# RiskChemi_Sensors_V2_12.net
KiCad netlist of a schematic drawn in Altium Designer
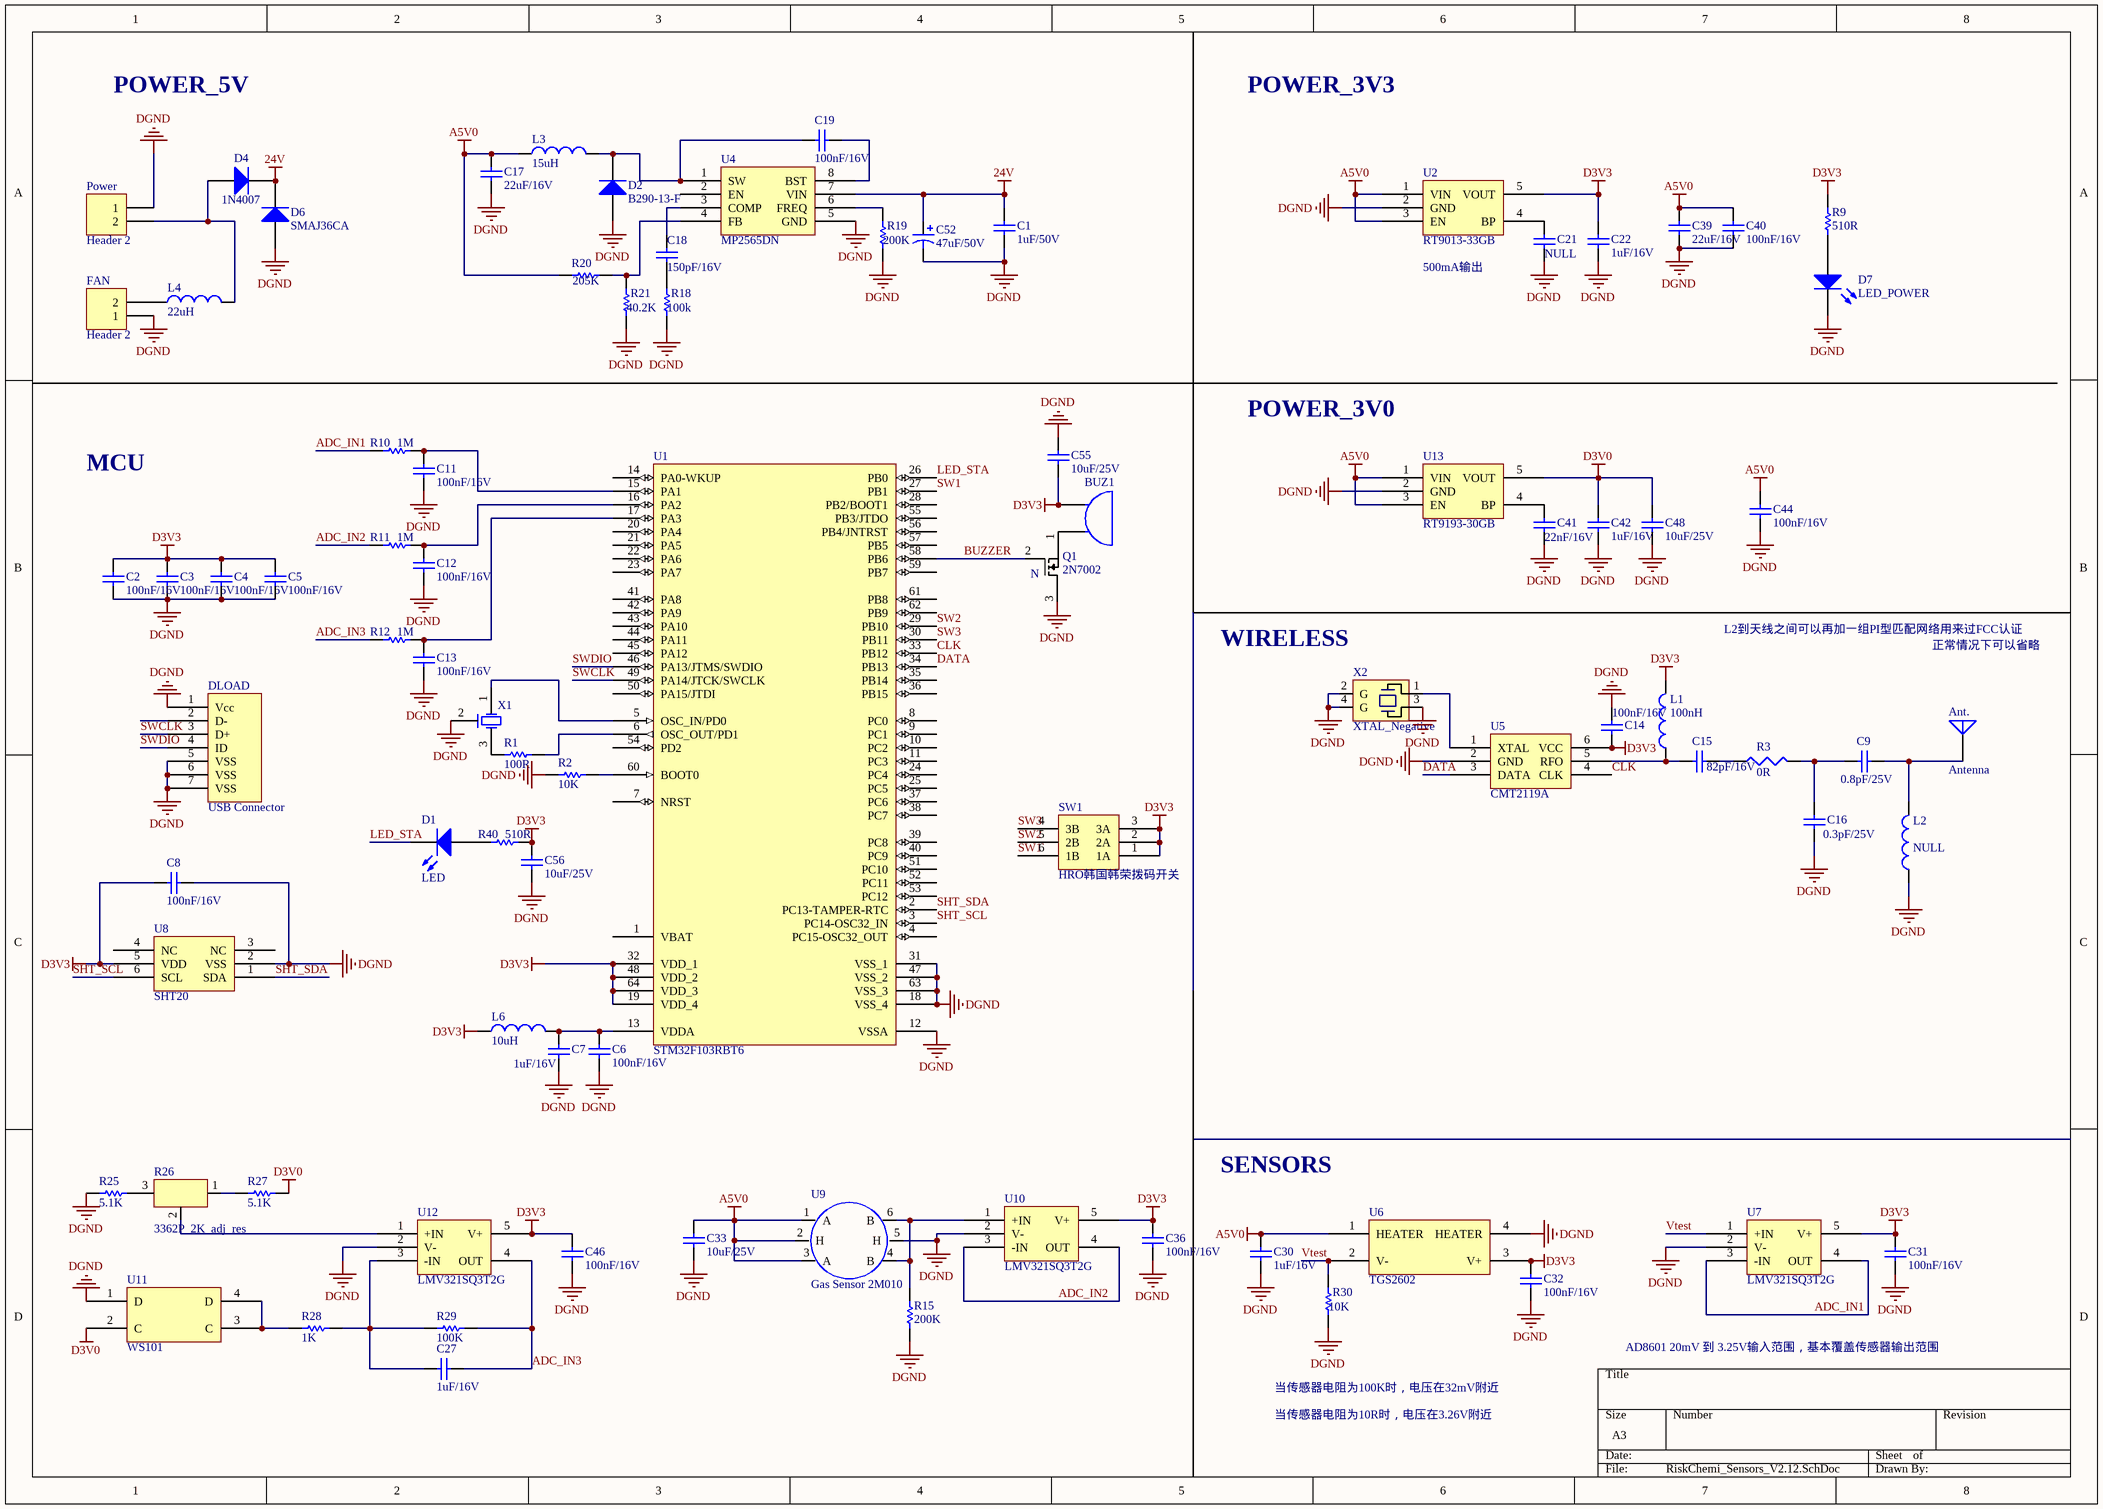
[diagram p0: RiskChemi_Sensors_V2.12.SchDoc]

(export (version "E")
  (design (tool "Eeschema 10.0.6"))
  (components
    (comp (ref "Ant.")
      (value "Antenna")
      (footprint "PIN1")
      (description "Generic Antenna")
      (fields (field (name "PUBLISHER") "Altium Limited"))
      (libsource (lib "Miscellaneous Devices") (part "Antenna"))
    )
    (comp (ref "BUZ1")
      (value "BUZZER 0905 through hole")
      (footprint "BUZ0905")
      (description "Buzzer")
      (libsource (lib "杂元件库") (part "BUZZER"))
    )
    (comp (ref "C1")
      (value "1uF/50V")
      (footprint "0805")
      (description "Capacitor")
      (fields (field (name "PUBLISHER") "Altium Limited"))
      (libsource (lib "Miscellaneous Devices") (part "Cap"))
    )
    (comp (ref "C2")
      (value "100nF/16V")
      (footprint "BinFeng:0603")
      (description "Capacitor")
      (fields (field (name "PUBLISHER") "Altium Limited"))
      (libsource (lib "Miscellaneous Devices") (part "Cap"))
    )
    (comp (ref "C3")
      (value "100nF/16V")
      (footprint "BinFeng:0603")
      (description "Capacitor")
      (fields (field (name "PUBLISHER") "Altium Limited"))
      (libsource (lib "Miscellaneous Devices") (part "Cap"))
    )
    (comp (ref "C4")
      (value "100nF/16V")
      (footprint "BinFeng:0603")
      (description "Capacitor")
      (fields (field (name "PUBLISHER") "Altium Limited"))
      (libsource (lib "Miscellaneous Devices") (part "Cap"))
    )
    (comp (ref "C5")
      (value "100nF/16V")
      (footprint "BinFeng:0603")
      (description "Capacitor")
      (fields (field (name "PUBLISHER") "Altium Limited"))
      (libsource (lib "Miscellaneous Devices") (part "Cap"))
    )
    (comp (ref "C6")
      (value "100nF/16V")
      (footprint "BinFeng:0603")
      (description "Capacitor")
      (fields (field (name "PUBLISHER") "Altium Limited"))
      (libsource (lib "Miscellaneous Devices") (part "Cap"))
    )
    (comp (ref "C7")
      (value "1uF/16V")
      (footprint "BinFeng:0603")
      (description "Capacitor")
      (fields (field (name "PUBLISHER") "Altium Limited"))
      (libsource (lib "Miscellaneous Devices") (part "Cap"))
    )
    (comp (ref "C8")
      (value "100nF/16V")
      (footprint "BinFeng:0603")
      (description "Capacitor")
      (fields (field (name "PUBLISHER") "Altium Limited"))
      (libsource (lib "Miscellaneous Devices") (part "Cap"))
    )
    (comp (ref "C9")
      (value "0.8pF/25V")
      (footprint "1608[0603]")
      (description "Capacitor (Semiconductor SIM Model)")
      (fields (field (name "PUBLISHER") "Altium Limited"))
      (libsource (lib "Miscellaneous Devices") (part "Cap Semi"))
    )
    (comp (ref "C11")
      (value "100nF/16V")
      (footprint "BinFeng:0603")
      (description "Capacitor")
      (fields (field (name "PUBLISHER") "Altium Limited"))
      (libsource (lib "Miscellaneous Devices") (part "Cap"))
    )
    (comp (ref "C12")
      (value "100nF/16V")
      (footprint "BinFeng:0603")
      (description "Capacitor")
      (fields (field (name "PUBLISHER") "Altium Limited"))
      (libsource (lib "Miscellaneous Devices") (part "Cap"))
    )
    (comp (ref "C13")
      (value "100nF/16V")
      (footprint "BinFeng:0603")
      (description "Capacitor")
      (fields (field (name "PUBLISHER") "Altium Limited"))
      (libsource (lib "Miscellaneous Devices") (part "Cap"))
    )
    (comp (ref "C14")
      (value "100nF/16V")
      (footprint "BinFeng:0402")
      (description "Capacitor")
      (fields (field (name "PUBLISHER") "Altium Limited"))
      (libsource (lib "Miscellaneous Devices") (part "Cap"))
    )
    (comp (ref "C15")
      (value "82pF/16V")
      (footprint "BinFeng:0402")
      (description "Capacitor")
      (fields (field (name "PUBLISHER") "Altium Limited"))
      (libsource (lib "Miscellaneous Devices") (part "Cap"))
    )
    (comp (ref "C16")
      (value "0.3pF/25V")
      (footprint "BinFeng:0402")
      (description "Capacitor")
      (fields (field (name "PUBLISHER") "Altium Limited"))
      (libsource (lib "Miscellaneous Devices") (part "Cap"))
    )
    (comp (ref "C17")
      (value "22uF/16V")
      (footprint "0805")
      (description "Capacitor,50V")
      (fields (field (name "PUBLISHER") "Altium Limited"))
      (libsource (lib "Miscellaneous Devices") (part "Cap"))
    )
    (comp (ref "C18")
      (value "150pF/16V")
      (footprint "BinFeng:0603")
      (description "Capacitor")
      (fields (field (name "PUBLISHER") "Altium Limited"))
      (libsource (lib "Miscellaneous Devices") (part "Cap"))
    )
    (comp (ref "C19")
      (value "100nF/16V")
      (footprint "BinFeng:0603")
      (description "Capacitor")
      (fields (field (name "PUBLISHER") "Altium Limited"))
      (libsource (lib "Miscellaneous Devices") (part "Cap"))
    )
    (comp (ref "C21")
      (value "NULL")
      (footprint "BinFeng:0402")
      (description "Capacitor")
      (fields (field (name "PUBLISHER") "Altium Limited"))
      (libsource (lib "Miscellaneous Devices") (part "Cap"))
    )
    (comp (ref "C22")
      (value "1uF/16V")
      (footprint "BinFeng:0402")
      (description "Capacitor")
      (fields (field (name "PUBLISHER") "Altium Limited"))
      (libsource (lib "Miscellaneous Devices") (part "Cap"))
    )
    (comp (ref "C27")
      (value "1uF/16V")
      (footprint "BinFeng:0603")
      (description "Capacitor")
      (fields (field (name "PUBLISHER") "Altium Limited"))
      (libsource (lib "Miscellaneous Devices") (part "Cap"))
    )
    (comp (ref "C30")
      (value "1uF/16V")
      (footprint "BinFeng:0603")
      (description "Capacitor")
      (fields (field (name "PUBLISHER") "Altium Limited"))
      (libsource (lib "Miscellaneous Devices") (part "Cap"))
    )
    (comp (ref "C31")
      (value "100nF/16V")
      (footprint "BinFeng:0603")
      (description "Capacitor")
      (fields (field (name "PUBLISHER") "Altium Limited"))
      (libsource (lib "Miscellaneous Devices") (part "Cap"))
    )
    (comp (ref "C32")
      (value "100nF/16V")
      (footprint "BinFeng:0603")
      (description "Capacitor")
      (fields (field (name "PUBLISHER") "Altium Limited"))
      (libsource (lib "Miscellaneous Devices") (part "Cap"))
    )
    (comp (ref "C33")
      (value "10uF/25V")
      (footprint "0805")
      (description "Capacitor")
      (fields (field (name "PUBLISHER") "Altium Limited"))
      (libsource (lib "Miscellaneous Devices") (part "Cap"))
    )
    (comp (ref "C36")
      (value "100nF/16V")
      (footprint "BinFeng:0603")
      (description "Capacitor")
      (fields (field (name "PUBLISHER") "Altium Limited"))
      (libsource (lib "Miscellaneous Devices") (part "Cap"))
    )
    (comp (ref "C39")
      (value "22uF/16V")
      (footprint "1206")
      (description "Capacitor")
      (fields (field (name "PUBLISHER") "Altium Limited"))
      (libsource (lib "Miscellaneous Devices") (part "Cap"))
    )
    (comp (ref "C40")
      (value "100nF/16V")
      (footprint "BinFeng:0402")
      (description "Capacitor")
      (fields (field (name "PUBLISHER") "Altium Limited"))
      (libsource (lib "Miscellaneous Devices") (part "Cap"))
    )
    (comp (ref "C41")
      (value "22nF/16V")
      (footprint "BinFeng:0402")
      (description "Capacitor")
      (fields (field (name "PUBLISHER") "Altium Limited"))
      (libsource (lib "Miscellaneous Devices") (part "Cap"))
    )
    (comp (ref "C42")
      (value "1uF/16V")
      (footprint "BinFeng:0402")
      (description "Capacitor")
      (fields (field (name "PUBLISHER") "Altium Limited"))
      (libsource (lib "Miscellaneous Devices") (part "Cap"))
    )
    (comp (ref "C44")
      (value "100nF/16V")
      (footprint "BinFeng:0402")
      (description "Capacitor")
      (fields (field (name "PUBLISHER") "Altium Limited"))
      (libsource (lib "Miscellaneous Devices") (part "Cap"))
    )
    (comp (ref "C46")
      (value "100nF/16V")
      (footprint "BinFeng:0603")
      (description "Capacitor")
      (fields (field (name "PUBLISHER") "Altium Limited"))
      (libsource (lib "Miscellaneous Devices") (part "Cap"))
    )
    (comp (ref "C48")
      (value "10uF/25V")
      (footprint "0805")
      (description "Capacitor")
      (fields (field (name "PUBLISHER") "Altium Limited"))
      (libsource (lib "Miscellaneous Devices") (part "Cap"))
    )
    (comp (ref "C52")
      (value "47uF/50V")
      (footprint "cap_pol_8*10.2")
      (description "Polarized Capacitor (Radial)")
      (fields (field (name "PUBLISHER") "Altium Limited"))
      (libsource (lib "Miscellaneous Devices") (part "Cap Pol1"))
    )
    (comp (ref "C55")
      (value "10uF/25V")
      (footprint "0805")
      (description "Capacitor")
      (fields (field (name "PUBLISHER") "Altium Limited"))
      (libsource (lib "Miscellaneous Devices") (part "Cap"))
    )
    (comp (ref "C56")
      (value "10uF/25V")
      (footprint "0805")
      (description "Capacitor")
      (fields (field (name "PUBLISHER") "Altium Limited"))
      (libsource (lib "Miscellaneous Devices") (part "Cap"))
    )
    (comp (ref "D1")
      (value "LED")
      (footprint "1206_LED")
      (description "Typical INFRARED GaAs LED")
      (fields (field (name "PUBLISHER") "Altium Limited"))
      (libsource (lib "Miscellaneous Devices") (part "LED0"))
    )
    (comp (ref "D2")
      (value "B290-13-F")
      (footprint "B290")
      (description "Default Diode")
      (fields (field (name "PUBLISHER") "Altium Limited"))
      (libsource (lib "Miscellaneous Devices") (part "Diode"))
    )
    (comp (ref "D4")
      (value "1N4007")
      (footprint "6032_pol")
      (description "1 Amp General Purpose Rectifier")
      (fields (field (name "PUBLISHER") "Altium Limited"))
      (libsource (lib "Miscellaneous Devices") (part "Diode 1N4007"))
    )
    (comp (ref "D6")
      (value "SMAJ36CA")
      (footprint "B290")
      (description "1 Amp General Purpose Rectifier")
      (fields (field (name "PUBLISHER") "Altium Limited"))
      (libsource (lib "Miscellaneous Devices") (part "Diode 1N4007"))
    )
    (comp (ref "D7")
      (value "LED_POWER")
      (footprint "1206_LED")
      (description "Typical INFRARED GaAs LED")
      (fields (field (name "PUBLISHER") "Altium Limited"))
      (libsource (lib "Miscellaneous Devices") (part "LED0"))
    )
    (comp (ref "DLOAD")
      (value "USB Connector")
      (footprint "Mini_USB")
      (libsource (lib "BinFeng_Connectors") (part "Component_1"))
    )
    (comp (ref "FAN")
      (value "Header 2")
      (footprint "HDR1X2")
      (description "Header, 2-Pin")
      (fields (field (name "PUBLISHER") "Altium Limited"))
      (libsource (lib "Miscellaneous Connectors") (part "Header 2"))
    )
    (comp (ref "L1")
      (value "100nH")
      (footprint "0603C")
      (description "Inductor")
      (fields (field (name "PUBLISHER") "Altium Limited"))
      (libsource (lib "Miscellaneous Devices") (part "Inductor"))
    )
    (comp (ref "L2")
      (value "NULL")
      (footprint "hg:0402")
      (description "Inductor")
      (fields (field (name "PUBLISHER") "Altium Limited"))
      (libsource (lib "Miscellaneous Devices") (part "Inductor"))
    )
    (comp (ref "L3")
      (value "15uH")
      (footprint "4*4 Inductor")
      (description "Inductor, 1A")
      (fields (field (name "PUBLISHER") "Altium Limited"))
      (libsource (lib "Miscellaneous Devices") (part "Inductor"))
    )
    (comp (ref "L4")
      (value "22uH")
      (footprint "10*10Inductor")
      (description "Inductor, 1A")
      (fields (field (name "PUBLISHER") "Altium Limited"))
      (libsource (lib "Miscellaneous Devices") (part "Inductor"))
    )
    (comp (ref "L6")
      (value "10uH")
      (footprint "0805")
      (description "Inductor")
      (fields (field (name "PUBLISHER") "Altium Limited"))
      (libsource (lib "Miscellaneous Devices") (part "Inductor"))
    )
    (comp (ref "Power")
      (value "Header 2")
      (footprint "HDR1X2")
      (description "Header, 2-Pin")
      (fields (field (name "PUBLISHER") "Altium Limited"))
      (libsource (lib "") (part "Header 2_1"))
    )
    (comp (ref "Q1") (value "2N7002") (footprint "2N7002") (libsource (lib "seeder") (part "N-MOSFET")))
    (comp (ref "R1")
      (value "100R")
      (footprint "BinFeng:0603")
      (description "Resistor")
      (fields (field (name "PUBLISHER") "Altium Limited"))
      (libsource (lib "Miscellaneous Devices") (part "Res1"))
    )
    (comp (ref "R2")
      (value "10K")
      (footprint "BinFeng:0603")
      (description "Resistor")
      (fields (field (name "PUBLISHER") "Altium Limited"))
      (libsource (lib "Miscellaneous Devices") (part "Res1"))
    )
    (comp (ref "R3")
      (value "0R")
      (footprint "J1-0603")
      (description "Resistor")
      (fields (field (name "PUBLISHER") "Altium Limited"))
      (libsource (lib "Miscellaneous Devices") (part "Res3"))
    )
    (comp (ref "R9")
      (value "510R")
      (footprint "BinFeng:0603")
      (description "Resistor")
      (fields (field (name "PUBLISHER") "Altium Limited"))
      (libsource (lib "Miscellaneous Devices") (part "Res1"))
    )
    (comp (ref "R10")
      (value "1M")
      (footprint "BinFeng:0603")
      (description "Resistor")
      (fields (field (name "PUBLISHER") "Altium Limited"))
      (libsource (lib "Miscellaneous Devices") (part "Res1"))
    )
    (comp (ref "R11")
      (value "1M")
      (footprint "BinFeng:0603")
      (description "Resistor")
      (fields (field (name "PUBLISHER") "Altium Limited"))
      (libsource (lib "Miscellaneous Devices") (part "Res1"))
    )
    (comp (ref "R12")
      (value "1M")
      (footprint "BinFeng:0603")
      (description "Resistor")
      (fields (field (name "PUBLISHER") "Altium Limited"))
      (libsource (lib "Miscellaneous Devices") (part "Res1"))
    )
    (comp (ref "R15")
      (value "200K")
      (footprint "BinFeng:0603C")
      (description "Resistor")
      (fields (field (name "Comment") "Res1") (field (name "PUBLISHER") "Altium Limited"))
      (libsource (lib "Miscellaneous Devices") (part "Res1"))
    )
    (comp (ref "R18")
      (value "100k")
      (footprint "BinFeng:0603")
      (description "Resistor")
      (fields (field (name "PUBLISHER") "Altium Limited"))
      (libsource (lib "Miscellaneous Devices") (part "Res1"))
    )
    (comp (ref "R19")
      (value "200K")
      (footprint "BinFeng:0402")
      (description "Resistor")
      (fields (field (name "PUBLISHER") "Altium Limited"))
      (libsource (lib "Miscellaneous Devices") (part "Res1"))
    )
    (comp (ref "R20")
      (value "205K")
      (footprint "BinFeng:0603")
      (description "Resistor")
      (fields (field (name "PUBLISHER") "Altium Limited"))
      (libsource (lib "Miscellaneous Devices") (part "Res1"))
    )
    (comp (ref "R21")
      (value "40.2K")
      (footprint "BinFeng:0603")
      (description "Resistor")
      (fields (field (name "PUBLISHER") "Altium Limited"))
      (libsource (lib "Miscellaneous Devices") (part "Res1"))
    )
    (comp (ref "R25")
      (value "5.1K")
      (footprint "BinFeng:0603")
      (description "Resistor")
      (fields (field (name "PUBLISHER") "Altium Limited"))
      (libsource (lib "Miscellaneous Devices") (part "Res1"))
    )
    (comp (ref "R26")
      (value "3362P_2K_adj_res")
      (footprint "res_adj")
      (libsource (lib "BinFeng_IC") (part "res_adj"))
    )
    (comp (ref "R27")
      (value "5.1K")
      (footprint "BinFeng:0603")
      (description "Resistor")
      (fields (field (name "PUBLISHER") "Altium Limited"))
      (libsource (lib "Miscellaneous Devices") (part "Res1"))
    )
    (comp (ref "R28")
      (value "1K")
      (footprint "BinFeng:0603")
      (description "Resistor")
      (fields (field (name "PUBLISHER") "Altium Limited"))
      (libsource (lib "Miscellaneous Devices") (part "Res1"))
    )
    (comp (ref "R29")
      (value "100K")
      (footprint "BinFeng:0603")
      (description "Resistor")
      (fields (field (name "PUBLISHER") "Altium Limited"))
      (libsource (lib "Miscellaneous Devices") (part "Res1"))
    )
    (comp (ref "R30")
      (value "10K")
      (footprint "BinFeng:0603")
      (description "Resistor")
      (fields (field (name "PUBLISHER") "Altium Limited"))
      (libsource (lib "Miscellaneous Devices") (part "Res1"))
    )
    (comp (ref "R40")
      (value "510R")
      (footprint "BinFeng:0603")
      (description "Resistor")
      (fields (field (name "PUBLISHER") "Altium Limited"))
      (libsource (lib "Miscellaneous Devices") (part "Res1"))
    )
    (comp (ref "SW1")
      (value "HRO韩国韩荣拨码开关")
      (footprint "SW_6P_HRO")
      (libsource (lib "BinFeng_IC") (part "SW_6P"))
    )
    (comp (ref "U1")
      (value "STM32F103RBT6")
      (footprint "LQFP64_N")
      (description "STM32 ARM-based 32-bit MCU with 64 Kbytes Flash, 64-pin LQFP, Industrial Temperature")
      (fields (field (name "PUBLISHER") "Altium Limited"))
      (libsource (lib "ST Microcontroller 32-Bit STM32") (part "STM32F103R8T6"))
    )
    (comp (ref "U2")
      (value "RT9013-33GB")
      (footprint "SOT-23-5")
      (libsource (lib "BinFeng_IC") (part "RT9193"))
    )
    (comp (ref "U4")
      (value "MP2565DN")
      (footprint "so-8")
      (description "DCDC 4.5V~28V input 1.8V ~5V output low power")
      (libsource (lib "BinFeng_IC") (part "MP1584"))
    )
    (comp (ref "U5")
      (value "CMT2119A")
      (footprint "sot23-6")
      (libsource (lib "BinFeng_IC") (part "CMT2119A"))
    )
    (comp (ref "U6")
      (value "TGS2602")
      (footprint "Gas Sensor TGS2602 Slot")
      (description "VOC sensor")
      (libsource (lib "BinFeng_IC") (part "TGS2602"))
    )
    (comp (ref "U7")
      (value "LMV321SQ3T2G")
      (footprint "SC-70-5")
      (libsource (lib "BinFeng_IC") (part "LMV321SQ3T2G"))
    )
    (comp (ref "U8") (value "SHT20") (footprint "SHT20") (libsource (lib "BinFeng_IC") (part "SHT20")))
    (comp (ref "U9")
      (value "Gas Sensor 2M010")
      (footprint "Gas Sensor 2M010 Slot")
      (libsource (lib "BinFeng_IC") (part "Gas Sensor"))
    )
    (comp (ref "U10")
      (value "LMV321SQ3T2G")
      (footprint "SC-70-5")
      (libsource (lib "BinFeng_IC") (part "LMV321SQ3T2G"))
    )
    (comp (ref "U11")
      (value "WS101")
      (footprint "Gas_Sensor_WS101_Slot")
      (libsource (lib "BinFeng_IC") (part "Gas Sensor_WS101"))
    )
    (comp (ref "U12")
      (value "LMV321SQ3T2G")
      (footprint "SC-70-5")
      (libsource (lib "BinFeng_IC") (part "LMV321SQ3T2G"))
    )
    (comp (ref "U13")
      (value "RT9193-30GB")
      (footprint "SOT-23-5")
      (libsource (lib "BinFeng_IC") (part "RT9193"))
    )
    (comp (ref "X1") (value "8M smd") (footprint "8Mhz_XTAL") (libsource (lib "Schlib1") (part "8M smd")))
    (comp (ref "X2")
      (value "XTAL_Negative")
      (footprint "XTAL3225")
      (libsource (lib "BinFeng_IC") (part "XTAL_Negative"))
    )
  )
  (nets
    (net (code "1") (name "/ADC_IN1") (class "Default")
      (node (ref "R10") (pin "1") (pinfunction "1_1") (pintype "passive"))
      (node (ref "U7") (pin "3") (pinfunction "-IN_3") (pintype "passive"))
      (node (ref "U7") (pin "4") (pinfunction "OUT_4") (pintype "passive"))
    )
    (net (code "2") (name "/ADC_IN2") (class "Default")
      (node (ref "R11") (pin "1") (pinfunction "1_1") (pintype "passive"))
      (node (ref "U10") (pin "3") (pinfunction "-IN_3") (pintype "passive"))
      (node (ref "U10") (pin "4") (pinfunction "OUT_4") (pintype "passive"))
    )
    (net (code "3") (name "/ADC_IN3") (class "Default")
      (node (ref "C27") (pin "1") (pinfunction "1_1") (pintype "passive"))
      (node (ref "R12") (pin "1") (pinfunction "1_1") (pintype "passive"))
      (node (ref "R29") (pin "2") (pinfunction "2_2") (pintype "passive"))
      (node (ref "U12") (pin "4") (pinfunction "OUT_4") (pintype "passive"))
    )
    (net (code "4") (name "/BUZZER") (class "Default")
      (node (ref "Q1") (pin "2") (pinfunction "G_2") (pintype "passive"))
      (node (ref "U1") (pin "58") (pinfunction "PB6_58") (pintype "bidirectional"))
    )
    (net (code "5") (name "/CLK") (class "Default")
      (node (ref "U1") (pin "33") (pinfunction "PB12_33") (pintype "bidirectional"))
      (node (ref "U5") (pin "4") (pinfunction "CLK_4") (pintype "passive"))
    )
    (net (code "6") (name "/DATA") (class "Default")
      (node (ref "U1") (pin "34") (pinfunction "PB13_34") (pintype "bidirectional"))
      (node (ref "U5") (pin "3") (pinfunction "DATA_3") (pintype "passive"))
    )
    (net (code "7") (name "/LED_STA") (class "Default")
      (node (ref "D1") (pin "2") (pinfunction "K_2") (pintype "passive"))
      (node (ref "U1") (pin "26") (pinfunction "PB0_26") (pintype "bidirectional"))
    )
    (net (code "8") (name "/SHT_SCL") (class "Default")
      (node (ref "U1") (pin "3") (pinfunction "PC14-OSC32_IN_3") (pintype "bidirectional"))
      (node (ref "U8") (pin "6") (pinfunction "SCL_6") (pintype "passive"))
    )
    (net (code "9") (name "/SHT_SDA") (class "Default")
      (node (ref "U1") (pin "2") (pinfunction "PC13-TAMPER-RTC_2") (pintype "bidirectional"))
      (node (ref "U8") (pin "1") (pinfunction "SDA_1") (pintype "passive"))
    )
    (net (code "10") (name "/SW1") (class "Default")
      (node (ref "SW1") (pin "6") (pinfunction "1B_6") (pintype "passive"))
      (node (ref "U1") (pin "27") (pinfunction "PB1_27") (pintype "bidirectional"))
    )
    (net (code "11") (name "/SW2") (class "Default")
      (node (ref "SW1") (pin "5") (pinfunction "2B_5") (pintype "passive"))
      (node (ref "U1") (pin "29") (pinfunction "PB10_29") (pintype "bidirectional"))
    )
    (net (code "12") (name "/SW3") (class "Default")
      (node (ref "SW1") (pin "4") (pinfunction "3B_4") (pintype "passive"))
      (node (ref "U1") (pin "30") (pinfunction "PB11_30") (pintype "bidirectional"))
    )
    (net (code "13") (name "/SWCLK") (class "Default")
      (node (ref "DLOAD") (pin "3") (pinfunction "D+_3") (pintype "passive"))
      (node (ref "U1") (pin "49") (pinfunction "PA14/JTCK/SWCLK_49") (pintype "bidirectional"))
    )
    (net (code "14") (name "/SWDIO") (class "Default")
      (node (ref "DLOAD") (pin "4") (pinfunction "ID_4") (pintype "passive"))
      (node (ref "U1") (pin "46") (pinfunction "PA13/JTMS/SWDIO_46") (pintype "bidirectional"))
    )
    (net (code "15") (name "/Vtest") (class "Default")
      (node (ref "R30") (pin "2") (pinfunction "2_2") (pintype "passive"))
      (node (ref "U6") (pin "2") (pinfunction "V-_2") (pintype "passive"))
      (node (ref "U7") (pin "1") (pinfunction "+IN_1") (pintype "passive"))
    )
    (net (code "16") (name "24V") (class "Default")
      (node (ref "C1") (pin "2") (pinfunction "2_2") (pintype "passive"))
      (node (ref "C52") (pin "1") (pinfunction "1_1") (pintype "passive"))
      (node (ref "D4") (pin "2") (pinfunction "K_2") (pintype "passive"))
      (node (ref "D6") (pin "2") (pinfunction "K_2") (pintype "passive"))
      (node (ref "U4") (pin "7") (pinfunction "VIN_7") (pintype "passive"))
    )
    (net (code "17") (name "A5V0") (class "Default")
      (node (ref "C17") (pin "2") (pinfunction "2_2") (pintype "passive"))
      (node (ref "C30") (pin "2") (pinfunction "2_2") (pintype "passive"))
      (node (ref "C33") (pin "2") (pinfunction "2_2") (pintype "passive"))
      (node (ref "C39") (pin "1") (pinfunction "1_1") (pintype "passive"))
      (node (ref "C40") (pin "2") (pinfunction "2_2") (pintype "passive"))
      (node (ref "C44") (pin "2") (pinfunction "2_2") (pintype "passive"))
      (node (ref "L3") (pin "1") (pinfunction "1_1") (pintype "passive"))
      (node (ref "R20") (pin "2") (pinfunction "2_2") (pintype "passive"))
      (node (ref "U13") (pin "1") (pinfunction "VIN_1") (pintype "passive"))
      (node (ref "U13") (pin "3") (pinfunction "EN_3") (pintype "passive"))
      (node (ref "U2") (pin "1") (pinfunction "VIN_1") (pintype "passive"))
      (node (ref "U2") (pin "3") (pinfunction "EN_3") (pintype "passive"))
      (node (ref "U6") (pin "1") (pinfunction "HEATER_1") (pintype "passive"))
      (node (ref "U9") (pin "1") (pinfunction "A_1") (pintype "passive"))
      (node (ref "U9") (pin "2") (pinfunction "H_2") (pintype "passive"))
      (node (ref "U9") (pin "3") (pinfunction "A_3") (pintype "passive"))
    )
    (net (code "18") (name "D3V0") (class "Default")
      (node (ref "C42") (pin "2") (pinfunction "2_2") (pintype "passive"))
      (node (ref "C48") (pin "2") (pinfunction "2_2") (pintype "passive"))
      (node (ref "R27") (pin "2") (pinfunction "2_2") (pintype "passive"))
      (node (ref "U11") (pin "2") (pinfunction "C_2") (pintype "passive"))
      (node (ref "U13") (pin "5") (pinfunction "VOUT_5") (pintype "passive"))
    )
    (net (code "19") (name "D3V3") (class "Default")
      (node (ref "BUZ1") (pin "1") (pinfunction "A_1") (pintype "passive"))
      (node (ref "C14") (pin "2") (pinfunction "2_2") (pintype "passive"))
      (node (ref "C2") (pin "2") (pinfunction "2_2") (pintype "passive"))
      (node (ref "C22") (pin "2") (pinfunction "2_2") (pintype "passive"))
      (node (ref "C3") (pin "2") (pinfunction "2_2") (pintype "passive"))
      (node (ref "C31") (pin "2") (pinfunction "2_2") (pintype "passive"))
      (node (ref "C32") (pin "2") (pinfunction "2_2") (pintype "passive"))
      (node (ref "C36") (pin "2") (pinfunction "2_2") (pintype "passive"))
      (node (ref "C4") (pin "2") (pinfunction "2_2") (pintype "passive"))
      (node (ref "C46") (pin "2") (pinfunction "2_2") (pintype "passive"))
      (node (ref "C5") (pin "2") (pinfunction "2_2") (pintype "passive"))
      (node (ref "C55") (pin "2") (pinfunction "2_2") (pintype "passive"))
      (node (ref "C56") (pin "2") (pinfunction "2_2") (pintype "passive"))
      (node (ref "C8") (pin "2") (pinfunction "2_2") (pintype "passive"))
      (node (ref "L1") (pin "2") (pinfunction "2_2") (pintype "passive"))
      (node (ref "L6") (pin "1") (pinfunction "1_1") (pintype "passive"))
      (node (ref "R40") (pin "2") (pinfunction "2_2") (pintype "passive"))
      (node (ref "R9") (pin "2") (pinfunction "2_2") (pintype "passive"))
      (node (ref "SW1") (pin "1") (pinfunction "1A_1") (pintype "passive"))
      (node (ref "SW1") (pin "2") (pinfunction "2A_2") (pintype "passive"))
      (node (ref "SW1") (pin "3") (pinfunction "3A_3") (pintype "passive"))
      (node (ref "U1") (pin "19") (pinfunction "VDD_4_19") (pintype "power_in"))
      (node (ref "U1") (pin "32") (pinfunction "VDD_1_32") (pintype "power_in"))
      (node (ref "U1") (pin "48") (pinfunction "VDD_2_48") (pintype "power_in"))
      (node (ref "U1") (pin "64") (pinfunction "VDD_3_64") (pintype "power_in"))
      (node (ref "U10") (pin "5") (pinfunction "V+_5") (pintype "passive"))
      (node (ref "U12") (pin "5") (pinfunction "V+_5") (pintype "passive"))
      (node (ref "U2") (pin "5") (pinfunction "VOUT_5") (pintype "passive"))
      (node (ref "U5") (pin "6") (pinfunction "VCC_6") (pintype "passive"))
      (node (ref "U6") (pin "3") (pinfunction "V+_3") (pintype "passive"))
      (node (ref "U7") (pin "5") (pinfunction "V+_5") (pintype "passive"))
      (node (ref "U8") (pin "5") (pinfunction "VDD_5") (pintype "passive"))
    )
    (net (code "20") (name "DGND") (class "Default")
      (node (ref "C1") (pin "1") (pinfunction "1_1") (pintype "passive"))
      (node (ref "C11") (pin "2") (pinfunction "2_2") (pintype "passive"))
      (node (ref "C12") (pin "1") (pinfunction "1_1") (pintype "passive"))
      (node (ref "C13") (pin "1") (pinfunction "1_1") (pintype "passive"))
      (node (ref "C14") (pin "1") (pinfunction "1_1") (pintype "passive"))
      (node (ref "C16") (pin "1") (pinfunction "1_1") (pintype "passive"))
      (node (ref "C17") (pin "1") (pinfunction "1_1") (pintype "passive"))
      (node (ref "C2") (pin "1") (pinfunction "1_1") (pintype "passive"))
      (node (ref "C21") (pin "1") (pinfunction "1_1") (pintype "passive"))
      (node (ref "C22") (pin "1") (pinfunction "1_1") (pintype "passive"))
      (node (ref "C3") (pin "1") (pinfunction "1_1") (pintype "passive"))
      (node (ref "C30") (pin "1") (pinfunction "1_1") (pintype "passive"))
      (node (ref "C31") (pin "1") (pinfunction "1_1") (pintype "passive"))
      (node (ref "C32") (pin "1") (pinfunction "1_1") (pintype "passive"))
      (node (ref "C33") (pin "1") (pinfunction "1_1") (pintype "passive"))
      (node (ref "C36") (pin "1") (pinfunction "1_1") (pintype "passive"))
      (node (ref "C39") (pin "2") (pinfunction "2_2") (pintype "passive"))
      (node (ref "C4") (pin "1") (pinfunction "1_1") (pintype "passive"))
      (node (ref "C40") (pin "1") (pinfunction "1_1") (pintype "passive"))
      (node (ref "C41") (pin "1") (pinfunction "1_1") (pintype "passive"))
      (node (ref "C42") (pin "1") (pinfunction "1_1") (pintype "passive"))
      (node (ref "C44") (pin "1") (pinfunction "1_1") (pintype "passive"))
      (node (ref "C46") (pin "1") (pinfunction "1_1") (pintype "passive"))
      (node (ref "C48") (pin "1") (pinfunction "1_1") (pintype "passive"))
      (node (ref "C5") (pin "1") (pinfunction "1_1") (pintype "passive"))
      (node (ref "C52") (pin "2") (pinfunction "2_2") (pintype "passive"))
      (node (ref "C55") (pin "1") (pinfunction "1_1") (pintype "passive"))
      (node (ref "C56") (pin "1") (pinfunction "1_1") (pintype "passive"))
      (node (ref "C6") (pin "1") (pinfunction "1_1") (pintype "passive"))
      (node (ref "C7") (pin "1") (pinfunction "1_1") (pintype "passive"))
      (node (ref "C8") (pin "1") (pinfunction "1_1") (pintype "passive"))
      (node (ref "D2") (pin "1") (pinfunction "A_1") (pintype "passive"))
      (node (ref "D6") (pin "1") (pinfunction "A_1") (pintype "passive"))
      (node (ref "D7") (pin "2") (pinfunction "K_2") (pintype "passive"))
      (node (ref "DLOAD") (pin "1") (pinfunction "Vcc_1") (pintype "passive"))
      (node (ref "DLOAD") (pin "5") (pinfunction "VSS_5") (pintype "passive"))
      (node (ref "DLOAD") (pin "6") (pinfunction "VSS_6") (pintype "passive"))
      (node (ref "DLOAD") (pin "7") (pinfunction "VSS_7") (pintype "passive"))
      (node (ref "FAN") (pin "1") (pinfunction "1_1") (pintype "passive"))
      (node (ref "L2") (pin "1") (pinfunction "1_1") (pintype "passive"))
      (node (ref "Power") (pin "1") (pinfunction "1_1") (pintype "passive"))
      (node (ref "Q1") (pin "3") (pinfunction "S_3") (pintype "passive"))
      (node (ref "R15") (pin "2") (pinfunction "2_2") (pintype "passive"))
      (node (ref "R18") (pin "1") (pinfunction "1_1") (pintype "passive"))
      (node (ref "R19") (pin "1") (pinfunction "1_1") (pintype "passive"))
      (node (ref "R2") (pin "1") (pinfunction "1_1") (pintype "passive"))
      (node (ref "R21") (pin "1") (pinfunction "1_1") (pintype "passive"))
      (node (ref "R25") (pin "1") (pinfunction "1_1") (pintype "passive"))
      (node (ref "R30") (pin "1") (pinfunction "1_1") (pintype "passive"))
      (node (ref "U1") (pin "12") (pinfunction "VSSA_12") (pintype "power_in"))
      (node (ref "U1") (pin "18") (pinfunction "VSS_4_18") (pintype "power_in"))
      (node (ref "U1") (pin "31") (pinfunction "VSS_1_31") (pintype "power_in"))
      (node (ref "U1") (pin "47") (pinfunction "VSS_2_47") (pintype "power_in"))
      (node (ref "U1") (pin "63") (pinfunction "VSS_3_63") (pintype "power_in"))
      (node (ref "U10") (pin "2") (pinfunction "V-_2") (pintype "passive"))
      (node (ref "U11") (pin "1") (pinfunction "D_1") (pintype "passive"))
      (node (ref "U12") (pin "2") (pinfunction "V-_2") (pintype "passive"))
      (node (ref "U13") (pin "2") (pinfunction "GND_2") (pintype "passive"))
      (node (ref "U2") (pin "2") (pinfunction "GND_2") (pintype "passive"))
      (node (ref "U4") (pin "5") (pinfunction "GND_5") (pintype "passive"))
      (node (ref "U5") (pin "2") (pinfunction "GND_2") (pintype "passive"))
      (node (ref "U6") (pin "4") (pinfunction "HEATER_4") (pintype "passive"))
      (node (ref "U7") (pin "2") (pinfunction "V-_2") (pintype "passive"))
      (node (ref "U8") (pin "2") (pinfunction "VSS_2") (pintype "passive"))
      (node (ref "U9") (pin "5") (pinfunction "H_5") (pintype "passive"))
      (node (ref "X1") (pin "2") (pinfunction "GND_2") (pintype "passive"))
      (node (ref "X2") (pin "2") (pinfunction "G_2") (pintype "passive"))
      (node (ref "X2") (pin "3") (pintype "passive"))
      (node (ref "X2") (pin "4") (pinfunction "G_4") (pintype "passive"))
    )
    (net (code "21") (name "Net-(Ant.-A)") (class "Default")
      (node (ref "Ant.") (pin "1") (pinfunction "A_1") (pintype "passive"))
      (node (ref "C9") (pin "2") (pinfunction "2_2") (pintype "passive"))
      (node (ref "L2") (pin "2") (pinfunction "2_2") (pintype "passive"))
    )
    (net (code "22") (name "Net-(BUZ1-B)") (class "Default")
      (node (ref "BUZ1") (pin "2") (pinfunction "B_2") (pintype "passive"))
      (node (ref "Q1") (pin "1") (pinfunction "D_1") (pintype "passive"))
    )
    (net (code "23") (name "Net-(C15-Pad2)") (class "Default")
      (node (ref "C15") (pin "2") (pinfunction "2_2") (pintype "passive"))
      (node (ref "R3") (pin "1") (pinfunction "1_1") (pintype "passive"))
    )
    (net (code "24") (name "Net-(C16-Pad2)") (class "Default")
      (node (ref "C16") (pin "2") (pinfunction "2_2") (pintype "passive"))
      (node (ref "C9") (pin "1") (pinfunction "1_1") (pintype "passive"))
      (node (ref "R3") (pin "2") (pinfunction "2_2") (pintype "passive"))
    )
    (net (code "25") (name "Net-(C18-Pad2)") (class "Default")
      (node (ref "C18") (pin "2") (pinfunction "2_2") (pintype "passive"))
      (node (ref "R18") (pin "2") (pinfunction "2_2") (pintype "passive"))
    )
    (net (code "26") (name "Net-(D1-A)") (class "Default")
      (node (ref "D1") (pin "1") (pinfunction "A_1") (pintype "passive"))
      (node (ref "R40") (pin "1") (pinfunction "1_1") (pintype "passive"))
    )
    (net (code "27") (name "Net-(D2-K)") (class "Default")
      (node (ref "C19") (pin "2") (pinfunction "2_2") (pintype "passive"))
      (node (ref "D2") (pin "2") (pinfunction "K_2") (pintype "passive"))
      (node (ref "L3") (pin "2") (pinfunction "2_2") (pintype "passive"))
      (node (ref "U4") (pin "1") (pinfunction "SW_1") (pintype "passive"))
    )
    (net (code "28") (name "Net-(D4-A)") (class "Default")
      (node (ref "D4") (pin "1") (pinfunction "A_1") (pintype "passive"))
      (node (ref "L4") (pin "2") (pinfunction "2_2") (pintype "passive"))
      (node (ref "Power") (pin "2") (pinfunction "2_2") (pintype "passive"))
    )
    (net (code "29") (name "Net-(D7-A)") (class "Default")
      (node (ref "D7") (pin "1") (pinfunction "A_1") (pintype "passive"))
      (node (ref "R9") (pin "1") (pinfunction "1_1") (pintype "passive"))
    )
    (net (code "30") (name "Net-(FAN-Pad2)") (class "Default")
      (node (ref "FAN") (pin "2") (pinfunction "2_2") (pintype "passive"))
      (node (ref "L4") (pin "1") (pinfunction "1_1") (pintype "passive"))
    )
    (net (code "31") (name "Net-(R25-Pad2)") (class "Default")
      (node (ref "R25") (pin "2") (pinfunction "2_2") (pintype "passive"))
      (node (ref "R26") (pin "3") (pintype "passive"))
    )
    (net (code "32") (name "Net-(R26-Pad1)") (class "Default")
      (node (ref "R26") (pin "1") (pintype "passive"))
      (node (ref "R27") (pin "1") (pinfunction "1_1") (pintype "passive"))
    )
    (net (code "33") (name "Net-(R28-Pad1)") (class "Default")
      (node (ref "R28") (pin "1") (pinfunction "1_1") (pintype "passive"))
      (node (ref "U11") (pin "3") (pinfunction "C_3") (pintype "passive"))
      (node (ref "U11") (pin "4") (pinfunction "D_4") (pintype "passive"))
    )
    (net (code "34") (name "Net-(U1-BOOT0)") (class "Default")
      (node (ref "R2") (pin "2") (pinfunction "2_2") (pintype "passive"))
      (node (ref "U1") (pin "60") (pinfunction "BOOT0_60") (pintype "input"))
    )
    (net (code "35") (name "Net-(U1-OSC_IN{slash}PD0)") (class "Default")
      (node (ref "U1") (pin "5") (pinfunction "OSC_IN/PD0_5") (pintype "input"))
      (node (ref "X1") (pin "1") (pinfunction "OSC1_1") (pintype "passive"))
    )
    (net (code "36") (name "Net-(U1-OSC_OUT{slash}PD1)") (class "Default")
      (node (ref "R1") (pin "2") (pinfunction "2_2") (pintype "passive"))
      (node (ref "U1") (pin "6") (pinfunction "OSC_OUT/PD1_6") (pintype "output"))
    )
    (net (code "37") (name "Net-(U1-PA1)") (class "Default")
      (node (ref "C11") (pin "1") (pinfunction "1_1") (pintype "passive"))
      (node (ref "R10") (pin "2") (pinfunction "2_2") (pintype "passive"))
      (node (ref "U1") (pin "15") (pinfunction "PA1_15") (pintype "bidirectional"))
    )
    (net (code "38") (name "Net-(U1-PA2)") (class "Default")
      (node (ref "C12") (pin "2") (pinfunction "2_2") (pintype "passive"))
      (node (ref "R11") (pin "2") (pinfunction "2_2") (pintype "passive"))
      (node (ref "U1") (pin "16") (pinfunction "PA2_16") (pintype "bidirectional"))
    )
    (net (code "39") (name "Net-(U1-PA3)") (class "Default")
      (node (ref "C13") (pin "2") (pinfunction "2_2") (pintype "passive"))
      (node (ref "R12") (pin "2") (pinfunction "2_2") (pintype "passive"))
      (node (ref "U1") (pin "17") (pinfunction "PA3_17") (pintype "bidirectional"))
    )
    (net (code "40") (name "Net-(U1-VDDA)") (class "Default")
      (node (ref "C6") (pin "2") (pinfunction "2_2") (pintype "passive"))
      (node (ref "C7") (pin "2") (pinfunction "2_2") (pintype "passive"))
      (node (ref "L6") (pin "2") (pinfunction "2_2") (pintype "passive"))
      (node (ref "U1") (pin "13") (pinfunction "VDDA_13") (pintype "power_in"))
    )
    (net (code "41") (name "Net-(U2-BP)") (class "Default")
      (node (ref "C21") (pin "2") (pinfunction "2_2") (pintype "passive"))
      (node (ref "U2") (pin "4") (pinfunction "BP_4") (pintype "passive"))
    )
    (net (code "42") (name "Net-(U4-BST)") (class "Default")
      (node (ref "C19") (pin "1") (pinfunction "1_1") (pintype "passive"))
      (node (ref "U4") (pin "8") (pinfunction "BST_8") (pintype "passive"))
    )
    (net (code "43") (name "Net-(U4-COMP)") (class "Default")
      (node (ref "C18") (pin "1") (pinfunction "1_1") (pintype "passive"))
      (node (ref "U4") (pin "3") (pinfunction "COMP_3") (pintype "passive"))
    )
    (net (code "44") (name "Net-(U4-FB)") (class "Default")
      (node (ref "R20") (pin "1") (pinfunction "1_1") (pintype "passive"))
      (node (ref "R21") (pin "2") (pinfunction "2_2") (pintype "passive"))
      (node (ref "U4") (pin "4") (pinfunction "FB_4") (pintype "passive"))
    )
    (net (code "45") (name "Net-(U4-FREQ)") (class "Default")
      (node (ref "R19") (pin "2") (pinfunction "2_2") (pintype "passive"))
      (node (ref "U4") (pin "6") (pinfunction "FREQ_6") (pintype "passive"))
    )
    (net (code "46") (name "Net-(U5-RFO)") (class "Default")
      (node (ref "C15") (pin "1") (pinfunction "1_1") (pintype "passive"))
      (node (ref "L1") (pin "1") (pinfunction "1_1") (pintype "passive"))
      (node (ref "U5") (pin "5") (pinfunction "RFO_5") (pintype "passive"))
    )
    (net (code "47") (name "Net-(U5-XTAL)") (class "Default")
      (node (ref "U5") (pin "1") (pinfunction "XTAL_1") (pintype "passive"))
      (node (ref "X2") (pin "1") (pintype "passive"))
    )
    (net (code "48") (name "Net-(U10-+IN)") (class "Default")
      (node (ref "R15") (pin "1") (pinfunction "1_1") (pintype "passive"))
      (node (ref "U10") (pin "1") (pinfunction "+IN_1") (pintype "passive"))
      (node (ref "U9") (pin "4") (pinfunction "B_4") (pintype "passive"))
      (node (ref "U9") (pin "6") (pinfunction "B_6") (pintype "passive"))
    )
    (net (code "49") (name "Net-(U12-+IN)") (class "Default")
      (node (ref "R26") (pin "2") (pintype "passive"))
      (node (ref "U12") (pin "1") (pinfunction "+IN_1") (pintype "passive"))
    )
    (net (code "50") (name "Net-(U12--IN)") (class "Default")
      (node (ref "C27") (pin "2") (pinfunction "2_2") (pintype "passive"))
      (node (ref "R28") (pin "2") (pinfunction "2_2") (pintype "passive"))
      (node (ref "R29") (pin "1") (pinfunction "1_1") (pintype "passive"))
      (node (ref "U12") (pin "3") (pinfunction "-IN_3") (pintype "passive"))
    )
    (net (code "51") (name "Net-(U13-BP)") (class "Default")
      (node (ref "C41") (pin "2") (pinfunction "2_2") (pintype "passive"))
      (node (ref "U13") (pin "4") (pinfunction "BP_4") (pintype "passive"))
    )
    (net (code "52") (name "Net-(X1-OSC2)") (class "Default")
      (node (ref "R1") (pin "1") (pinfunction "1_1") (pintype "passive"))
      (node (ref "X1") (pin "3") (pinfunction "OSC2_3") (pintype "passive"))
    )
    (net (code "53") (name "unconnected-(DLOAD-D--Pad2)") (class "Default")
      (node (ref "DLOAD") (pin "2") (pinfunction "D-_2") (pintype "passive"))
    )
    (net (code "54") (name "unconnected-(U1-NRST-Pad7)") (class "Default")
      (node (ref "U1") (pin "7") (pinfunction "NRST_7") (pintype "bidirectional"))
    )
    (net (code "55") (name "unconnected-(U1-PA0-WKUP-Pad14)") (class "Default")
      (node (ref "U1") (pin "14") (pinfunction "PA0-WKUP_14") (pintype "bidirectional"))
    )
    (net (code "56") (name "unconnected-(U1-PA4-Pad20)") (class "Default")
      (node (ref "U1") (pin "20") (pinfunction "PA4_20") (pintype "bidirectional"))
    )
    (net (code "57") (name "unconnected-(U1-PA5-Pad21)") (class "Default")
      (node (ref "U1") (pin "21") (pinfunction "PA5_21") (pintype "bidirectional"))
    )
    (net (code "58") (name "unconnected-(U1-PA6-Pad22)") (class "Default")
      (node (ref "U1") (pin "22") (pinfunction "PA6_22") (pintype "bidirectional"))
    )
    (net (code "59") (name "unconnected-(U1-PA7-Pad23)") (class "Default")
      (node (ref "U1") (pin "23") (pinfunction "PA7_23") (pintype "bidirectional"))
    )
    (net (code "60") (name "unconnected-(U1-PA8-Pad41)") (class "Default")
      (node (ref "U1") (pin "41") (pinfunction "PA8_41") (pintype "bidirectional"))
    )
    (net (code "61") (name "unconnected-(U1-PA9-Pad42)") (class "Default")
      (node (ref "U1") (pin "42") (pinfunction "PA9_42") (pintype "bidirectional"))
    )
    (net (code "62") (name "unconnected-(U1-PA10-Pad43)") (class "Default")
      (node (ref "U1") (pin "43") (pinfunction "PA10_43") (pintype "bidirectional"))
    )
    (net (code "63") (name "unconnected-(U1-PA11-Pad44)") (class "Default")
      (node (ref "U1") (pin "44") (pinfunction "PA11_44") (pintype "bidirectional"))
    )
    (net (code "64") (name "unconnected-(U1-PA12-Pad45)") (class "Default")
      (node (ref "U1") (pin "45") (pinfunction "PA12_45") (pintype "bidirectional"))
    )
    (net (code "65") (name "unconnected-(U1-PA15{slash}JTDI-Pad50)") (class "Default")
      (node (ref "U1") (pin "50") (pinfunction "PA15/JTDI_50") (pintype "bidirectional"))
    )
    (net (code "66") (name "unconnected-(U1-PB2{slash}BOOT1-Pad28)") (class "Default")
      (node (ref "U1") (pin "28") (pinfunction "PB2/BOOT1_28") (pintype "bidirectional"))
    )
    (net (code "67") (name "unconnected-(U1-PB3{slash}JTDO-Pad55)") (class "Default")
      (node (ref "U1") (pin "55") (pinfunction "PB3/JTDO_55") (pintype "bidirectional"))
    )
    (net (code "68") (name "unconnected-(U1-PB4{slash}JNTRST-Pad56)") (class "Default")
      (node (ref "U1") (pin "56") (pinfunction "PB4/JNTRST_56") (pintype "bidirectional"))
    )
    (net (code "69") (name "unconnected-(U1-PB5-Pad57)") (class "Default")
      (node (ref "U1") (pin "57") (pinfunction "PB5_57") (pintype "bidirectional"))
    )
    (net (code "70") (name "unconnected-(U1-PB7-Pad59)") (class "Default")
      (node (ref "U1") (pin "59") (pinfunction "PB7_59") (pintype "bidirectional"))
    )
    (net (code "71") (name "unconnected-(U1-PB8-Pad61)") (class "Default")
      (node (ref "U1") (pin "61") (pinfunction "PB8_61") (pintype "bidirectional"))
    )
    (net (code "72") (name "unconnected-(U1-PB9-Pad62)") (class "Default")
      (node (ref "U1") (pin "62") (pinfunction "PB9_62") (pintype "bidirectional"))
    )
    (net (code "73") (name "unconnected-(U1-PB14-Pad35)") (class "Default")
      (node (ref "U1") (pin "35") (pinfunction "PB14_35") (pintype "bidirectional"))
    )
    (net (code "74") (name "unconnected-(U1-PB15-Pad36)") (class "Default")
      (node (ref "U1") (pin "36") (pinfunction "PB15_36") (pintype "bidirectional"))
    )
    (net (code "75") (name "unconnected-(U1-PC0-Pad8)") (class "Default")
      (node (ref "U1") (pin "8") (pinfunction "PC0_8") (pintype "bidirectional"))
    )
    (net (code "76") (name "unconnected-(U1-PC1-Pad9)") (class "Default")
      (node (ref "U1") (pin "9") (pinfunction "PC1_9") (pintype "bidirectional"))
    )
    (net (code "77") (name "unconnected-(U1-PC2-Pad10)") (class "Default")
      (node (ref "U1") (pin "10") (pinfunction "PC2_10") (pintype "bidirectional"))
    )
    (net (code "78") (name "unconnected-(U1-PC3-Pad11)") (class "Default")
      (node (ref "U1") (pin "11") (pinfunction "PC3_11") (pintype "bidirectional"))
    )
    (net (code "79") (name "unconnected-(U1-PC4-Pad24)") (class "Default")
      (node (ref "U1") (pin "24") (pinfunction "PC4_24") (pintype "bidirectional"))
    )
    (net (code "80") (name "unconnected-(U1-PC5-Pad25)") (class "Default")
      (node (ref "U1") (pin "25") (pinfunction "PC5_25") (pintype "bidirectional"))
    )
    (net (code "81") (name "unconnected-(U1-PC6-Pad37)") (class "Default")
      (node (ref "U1") (pin "37") (pinfunction "PC6_37") (pintype "bidirectional"))
    )
    (net (code "82") (name "unconnected-(U1-PC7-Pad38)") (class "Default")
      (node (ref "U1") (pin "38") (pinfunction "PC7_38") (pintype "bidirectional"))
    )
    (net (code "83") (name "unconnected-(U1-PC8-Pad39)") (class "Default")
      (node (ref "U1") (pin "39") (pinfunction "PC8_39") (pintype "bidirectional"))
    )
    (net (code "84") (name "unconnected-(U1-PC9-Pad40)") (class "Default")
      (node (ref "U1") (pin "40") (pinfunction "PC9_40") (pintype "bidirectional"))
    )
    (net (code "85") (name "unconnected-(U1-PC10-Pad51)") (class "Default")
      (node (ref "U1") (pin "51") (pinfunction "PC10_51") (pintype "bidirectional"))
    )
    (net (code "86") (name "unconnected-(U1-PC11-Pad52)") (class "Default")
      (node (ref "U1") (pin "52") (pinfunction "PC11_52") (pintype "bidirectional"))
    )
    (net (code "87") (name "unconnected-(U1-PC12-Pad53)") (class "Default")
      (node (ref "U1") (pin "53") (pinfunction "PC12_53") (pintype "bidirectional"))
    )
    (net (code "88") (name "unconnected-(U1-PC15-OSC32_OUT-Pad4)") (class "Default")
      (node (ref "U1") (pin "4") (pinfunction "PC15-OSC32_OUT_4") (pintype "bidirectional"))
    )
    (net (code "89") (name "unconnected-(U1-PD2-Pad54)") (class "Default")
      (node (ref "U1") (pin "54") (pinfunction "PD2_54") (pintype "bidirectional"))
    )
    (net (code "90") (name "unconnected-(U1-VBAT-Pad1)") (class "Default")
      (node (ref "U1") (pin "1") (pinfunction "VBAT_1") (pintype "power_in"))
    )
    (net (code "91") (name "unconnected-(U4-EN-Pad2)") (class "Default")
      (node (ref "U4") (pin "2") (pinfunction "EN_2") (pintype "passive"))
    )
    (net (code "92") (name "unconnected-(U8-NC-Pad3)") (class "Default")
      (node (ref "U8") (pin "3") (pinfunction "NC_3") (pintype "passive"))
    )
    (net (code "93") (name "unconnected-(U8-NC-Pad4)") (class "Default")
      (node (ref "U8") (pin "4") (pinfunction "NC_4") (pintype "passive"))
    )
  )
)
